# main_card_relay.net
KiCad netlist of a schematic drawn in EAGLE
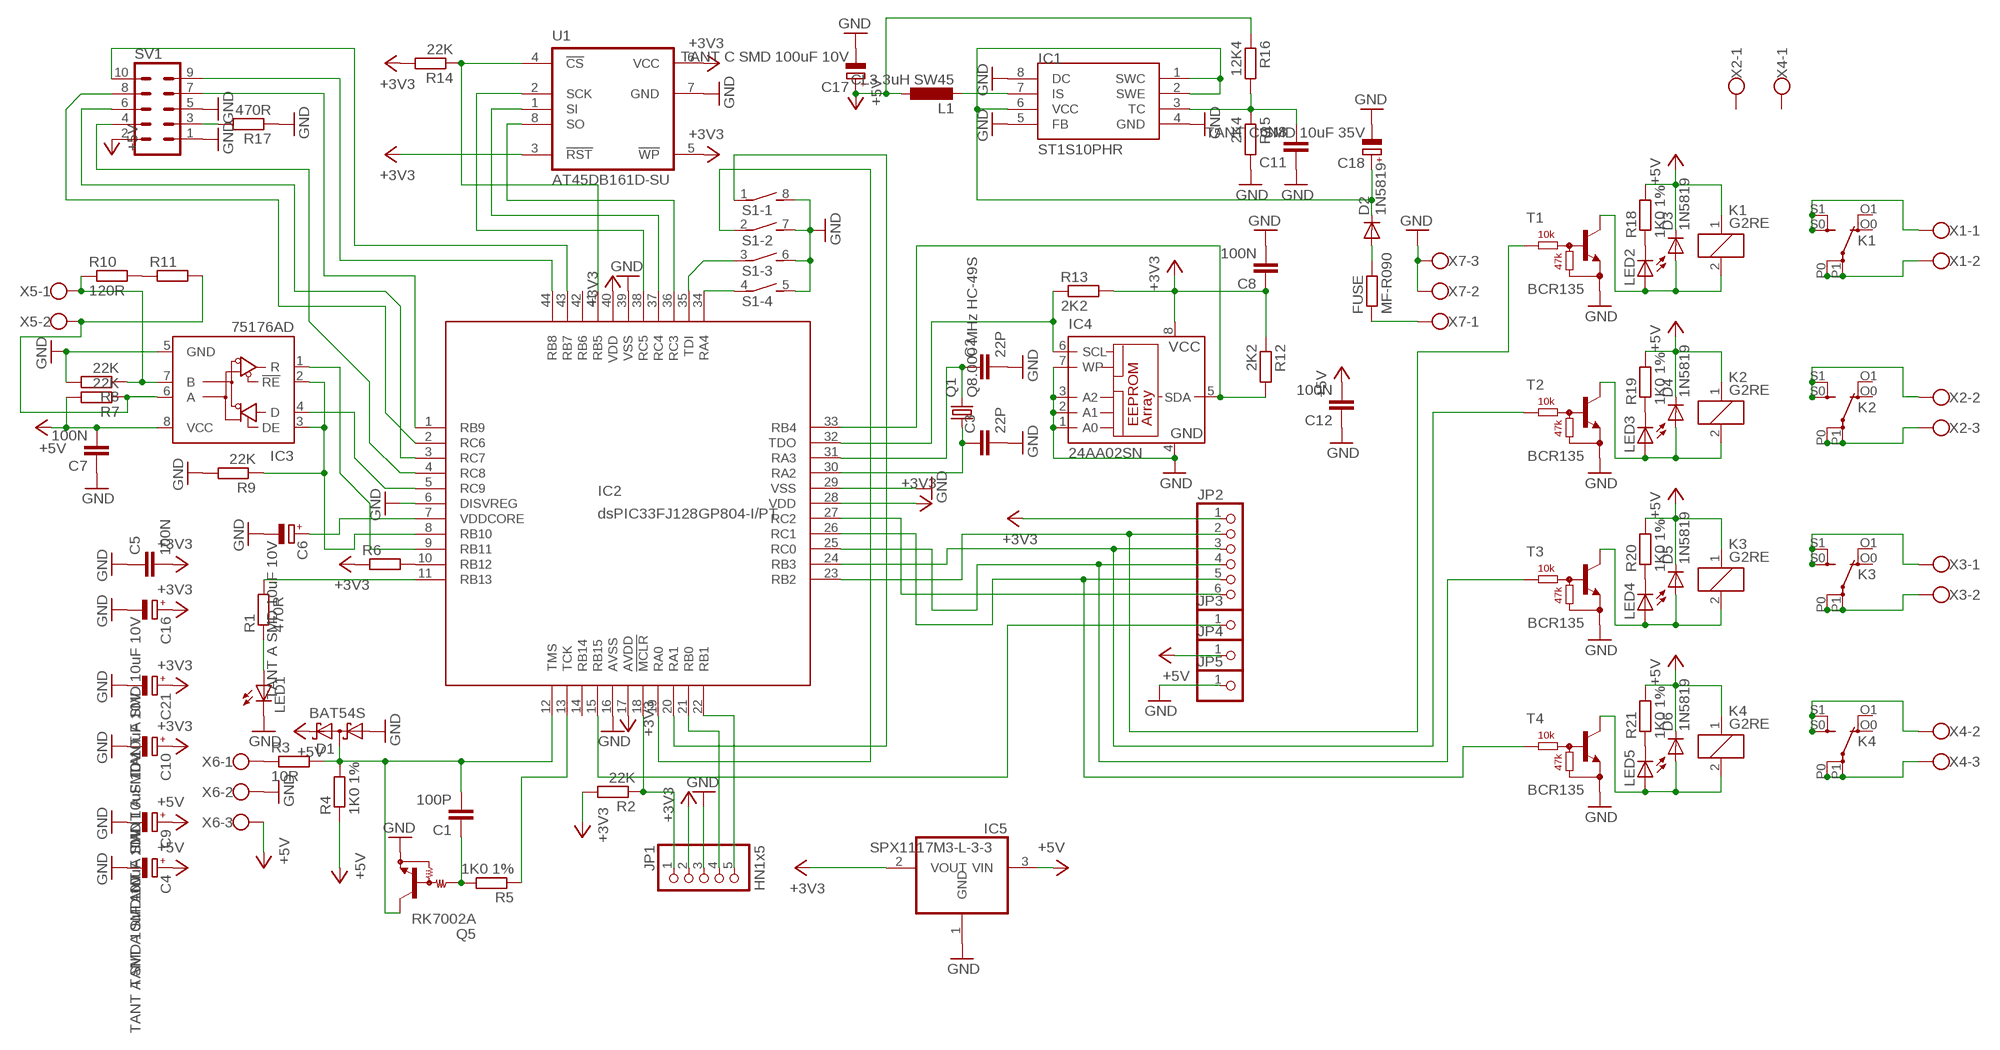
[diagram p0: schematic, sheet 1]

(export (version "E")
  (design (tool "Eeschema 10.0.6"))
  (components
    (comp (ref "C1")
      (value "100P")
      (footprint "eagle-import:C0805")
      (libsource (lib "eagle-import") (part "C-EUC0805"))
    )
    (comp (ref "C2")
      (value "22P")
      (footprint "eagle-import:C0805")
      (libsource (lib "eagle-import") (part "C-EUC0805"))
    )
    (comp (ref "C3")
      (value "22P")
      (footprint "eagle-import:C0805")
      (libsource (lib "eagle-import") (part "C-EUC0805"))
    )
    (comp (ref "C4")
      (value "TANT A SMD 10uF 10V")
      (footprint "eagle-import:SMC_A")
      (libsource (lib "eagle-import") (part "CPOL-EUSMCA"))
    )
    (comp (ref "C5")
      (value "100N")
      (footprint "eagle-import:C0805")
      (libsource (lib "eagle-import") (part "C-EUC0805"))
    )
    (comp (ref "C6")
      (value "TANT A SMD 10uF 10V")
      (footprint "eagle-import:SMC_A")
      (libsource (lib "eagle-import") (part "CPOL-EUSMCA"))
    )
    (comp (ref "C7")
      (value "100N")
      (footprint "eagle-import:C0805")
      (libsource (lib "eagle-import") (part "C-EUC0805"))
    )
    (comp (ref "C8")
      (value "100N")
      (footprint "eagle-import:C0805")
      (libsource (lib "eagle-import") (part "C-EUC0805"))
    )
    (comp (ref "C9")
      (value "TANT A SMD 10uF 10V")
      (footprint "eagle-import:SMC_A")
      (libsource (lib "eagle-import") (part "CPOL-EUSMCA"))
    )
    (comp (ref "C10")
      (value "TANT A SMD 10uF 10V")
      (footprint "eagle-import:SMC_A")
      (libsource (lib "eagle-import") (part "CPOL-EUSMCA"))
    )
    (comp (ref "C11")
      (value "6N8")
      (footprint "eagle-import:C0805")
      (libsource (lib "eagle-import") (part "C-EUC0805"))
    )
    (comp (ref "C12")
      (value "100N")
      (footprint "eagle-import:C0805")
      (libsource (lib "eagle-import") (part "C-EUC0805"))
    )
    (comp (ref "C16")
      (value "TANT A SMD 10uF 10V")
      (footprint "eagle-import:SMC_A")
      (libsource (lib "eagle-import") (part "CPOL-EUSMCA"))
    )
    (comp (ref "C17")
      (value "TANT C SMD 100uF 10V")
      (footprint "eagle-import:SMC_C")
      (libsource (lib "eagle-import") (part "CPOL-EUSMCC"))
    )
    (comp (ref "C18")
      (value "TANT C SMD 10uF 35V")
      (footprint "eagle-import:SMC_C")
      (libsource (lib "eagle-import") (part "CPOL-EUSMCC"))
    )
    (comp (ref "C21")
      (value "TANT A SMD 10uF 10V")
      (footprint "eagle-import:SMC_A")
      (libsource (lib "eagle-import") (part "CPOL-EUSMCA"))
    )
    (comp (ref "D1")
      (value "BAT54S")
      (footprint "eagle-import:SOT23")
      (libsource (lib "eagle-import") (part "BAS40-04"))
    )
    (comp (ref "D2")
      (value "1N5819")
      (footprint "eagle-import:DO214AC")
      (libsource (lib "eagle-import") (part "DIODE-DO214AC"))
    )
    (comp (ref "D3")
      (value "1N5819")
      (footprint "eagle-import:DO214AC")
      (libsource (lib "eagle-import") (part "DIODE-DO214AC"))
    )
    (comp (ref "D4")
      (value "1N5819")
      (footprint "eagle-import:DO214AC")
      (libsource (lib "eagle-import") (part "DIODE-DO214AC"))
    )
    (comp (ref "D5")
      (value "1N5819")
      (footprint "eagle-import:DO214AC")
      (libsource (lib "eagle-import") (part "DIODE-DO214AC"))
    )
    (comp (ref "D6")
      (value "1N5819")
      (footprint "eagle-import:DO214AC")
      (libsource (lib "eagle-import") (part "DIODE-DO214AC"))
    )
    (comp (ref "FUSE")
      (value "MF-R090")
      (footprint "eagle-import:0204V")
      (libsource (lib "eagle-import") (part "R-EU_0204/2V"))
    )
    (comp (ref "IC1")
      (value "ST1S10PHR")
      (footprint "eagle-import:SOIC8")
      (libsource (lib "eagle-import") (part "MC34063AD"))
    )
    (comp (ref "IC2")
      (value "dsPIC33FJ128GP804-I/PT")
      (footprint "eagle-import:TQFP44")
      (libsource (lib "eagle-import") (part "PIC24FJ64GA004"))
    )
    (comp (ref "IC3")
      (value "75176AD")
      (footprint "eagle-import:D_R-PDSO-G8")
      (libsource (lib "eagle-import") (part "75176AD"))
    )
    (comp (ref "IC4")
      (value "24AA02SN")
      (footprint "eagle-import:SO-08")
      (fields (field (name "MPN") "24AA02/SN"))
      (libsource (lib "eagle-import") (part "24SNAA02"))
    )
    (comp (ref "IC5")
      (value "SPX1117M3-L-3-3")
      (footprint "eagle-import:SOT223")
      (fields (field (name "MPN") "REG1117"))
      (libsource (lib "eagle-import") (part "REG1117"))
    )
    (comp (ref "JP1")
      (value "HN1x5")
      (footprint "eagle-import:1X05")
      (libsource (lib "eagle-import") (part "PINHD-1X5"))
    )
    (comp (ref "JP2")
      (value "PINHD-1X6")
      (footprint "eagle-import:1X06")
      (libsource (lib "eagle-import") (part "PINHD-1X6"))
    )
    (comp (ref "JP3")
      (value "PINHD-1X1")
      (footprint "eagle-import:1X01")
      (libsource (lib "eagle-import") (part "PINHD-1X1"))
    )
    (comp (ref "JP4")
      (value "PINHD-1X1")
      (footprint "eagle-import:1X01")
      (libsource (lib "eagle-import") (part "PINHD-1X1"))
    )
    (comp (ref "JP5")
      (value "PINHD-1X1")
      (footprint "eagle-import:1X01")
      (libsource (lib "eagle-import") (part "PINHD-1X1"))
    )
    (comp (ref "K1")
      (value "G2RE")
      (footprint "eagle-import:G2RE")
      (libsource (lib "eagle-import") (part "G2RE"))
    )
    (comp (ref "K2")
      (value "G2RE")
      (footprint "eagle-import:G2RE")
      (libsource (lib "eagle-import") (part "G2RE"))
    )
    (comp (ref "K3")
      (value "G2RE")
      (footprint "eagle-import:G2RE")
      (libsource (lib "eagle-import") (part "G2RE"))
    )
    (comp (ref "K4")
      (value "G2RE")
      (footprint "eagle-import:G2RE")
      (libsource (lib "eagle-import") (part "G2RE"))
    )
    (comp (ref "L1")
      (value "CL3.3uH SW45")
      (footprint "eagle-import:0207_2V")
      (libsource (lib "eagle-import") (part "L-EU0207/2V"))
    )
    (comp (ref "LED1")
      (value "LEDCHIPLED_1206")
      (footprint "eagle-import:CHIPLED_1206")
      (libsource (lib "eagle-import") (part "LEDCHIPLED_1206"))
    )
    (comp (ref "LED2")
      (value "LEDCHIPLED_1206")
      (footprint "eagle-import:CHIPLED_1206")
      (libsource (lib "eagle-import") (part "LEDCHIPLED_1206"))
    )
    (comp (ref "LED3")
      (value "LEDCHIPLED_1206")
      (footprint "eagle-import:CHIPLED_1206")
      (libsource (lib "eagle-import") (part "LEDCHIPLED_1206"))
    )
    (comp (ref "LED4")
      (value "LEDCHIPLED_1206")
      (footprint "eagle-import:CHIPLED_1206")
      (libsource (lib "eagle-import") (part "LEDCHIPLED_1206"))
    )
    (comp (ref "LED5")
      (value "LEDCHIPLED_1206")
      (footprint "eagle-import:CHIPLED_1206")
      (libsource (lib "eagle-import") (part "LEDCHIPLED_1206"))
    )
    (comp (ref "Q1")
      (value "Q8.000 MHz HC-49S")
      (footprint "eagle-import:HC49_S")
      (libsource (lib "eagle-import") (part "CRYSTALHC49S"))
    )
    (comp (ref "Q5")
      (value "RK7002A")
      (footprint "eagle-import:SC59-BEC")
      (libsource (lib "eagle-import") (part "MUN2214T1"))
    )
    (comp (ref "R1")
      (value "470R")
      (footprint "eagle-import:R0805")
      (libsource (lib "eagle-import") (part "R-EU_R0805"))
    )
    (comp (ref "R2")
      (value "22K")
      (footprint "eagle-import:R0805")
      (libsource (lib "eagle-import") (part "R-EU_R0805"))
    )
    (comp (ref "R3")
      (value "10R")
      (footprint "eagle-import:R0805")
      (libsource (lib "eagle-import") (part "R-EU_R0805"))
    )
    (comp (ref "R4")
      (value "1K0 1%")
      (footprint "eagle-import:R0805")
      (libsource (lib "eagle-import") (part "R-EU_R0805"))
    )
    (comp (ref "R5")
      (value "1K0 1%")
      (footprint "eagle-import:R0805")
      (libsource (lib "eagle-import") (part "R-EU_R0805"))
    )
    (comp (ref "R6")
      (value "R-EU_R0201")
      (footprint "eagle-import:R0201")
      (libsource (lib "eagle-import") (part "R-EU_R0201"))
    )
    (comp (ref "R7")
      (value "22K")
      (footprint "eagle-import:R0805")
      (libsource (lib "eagle-import") (part "R-EU_R0805"))
    )
    (comp (ref "R8")
      (value "22K")
      (footprint "eagle-import:R0805")
      (libsource (lib "eagle-import") (part "R-EU_R0805"))
    )
    (comp (ref "R9")
      (value "22K")
      (footprint "eagle-import:R0805")
      (libsource (lib "eagle-import") (part "R-EU_R0805"))
    )
    (comp (ref "R10")
      (value "120R")
      (footprint "eagle-import:R0805")
      (libsource (lib "eagle-import") (part "R-EU_R0805"))
    )
    (comp (ref "R11")
      (value "R-EU_R0201")
      (footprint "eagle-import:R0201")
      (libsource (lib "eagle-import") (part "R-EU_R0201"))
    )
    (comp (ref "R12")
      (value "2K2")
      (footprint "eagle-import:R0805")
      (libsource (lib "eagle-import") (part "R-EU_R0805"))
    )
    (comp (ref "R13")
      (value "2K2")
      (footprint "eagle-import:R0805")
      (libsource (lib "eagle-import") (part "R-EU_R0805"))
    )
    (comp (ref "R14")
      (value "22K")
      (footprint "eagle-import:R0805")
      (libsource (lib "eagle-import") (part "R-EU_R0805"))
    )
    (comp (ref "R15")
      (value "2K4")
      (footprint "eagle-import:R0805")
      (libsource (lib "eagle-import") (part "R-EU_R0805"))
    )
    (comp (ref "R16")
      (value "12K4")
      (footprint "eagle-import:R0805")
      (libsource (lib "eagle-import") (part "R-EU_R0805"))
    )
    (comp (ref "R17")
      (value "470R")
      (footprint "eagle-import:R0805")
      (libsource (lib "eagle-import") (part "R-EU_R0805"))
    )
    (comp (ref "R18")
      (value "1K0 1%")
      (footprint "eagle-import:R0805")
      (libsource (lib "eagle-import") (part "R-EU_R0805"))
    )
    (comp (ref "R19")
      (value "1K0 1%")
      (footprint "eagle-import:R0805")
      (libsource (lib "eagle-import") (part "R-EU_R0805"))
    )
    (comp (ref "R20")
      (value "1K0 1%")
      (footprint "eagle-import:R0805")
      (libsource (lib "eagle-import") (part "R-EU_R0805"))
    )
    (comp (ref "R21")
      (value "1K0 1%")
      (footprint "eagle-import:R0805")
      (libsource (lib "eagle-import") (part "R-EU_R0805"))
    )
    (comp (ref "S1")
      (value "DIP04S")
      (footprint "eagle-import:DIP04S")
      (libsource (lib "eagle-import") (part "DIP04S"))
    )
    (comp (ref "SV1")
      (value "ML10")
      (footprint "eagle-import:ML10")
      (libsource (lib "eagle-import") (part "ML10"))
    )
    (comp (ref "T1")
      (value "BCR135")
      (footprint "eagle-import:SOT23-R_INFINEON")
      (libsource (lib "eagle-import") (part "BCR135"))
    )
    (comp (ref "T2")
      (value "BCR135")
      (footprint "eagle-import:SOT23-R_INFINEON")
      (libsource (lib "eagle-import") (part "BCR135"))
    )
    (comp (ref "T3")
      (value "BCR135")
      (footprint "eagle-import:SOT23-R_INFINEON")
      (libsource (lib "eagle-import") (part "BCR135"))
    )
    (comp (ref "T4")
      (value "BCR135")
      (footprint "eagle-import:SOT23-R_INFINEON")
      (libsource (lib "eagle-import") (part "BCR135"))
    )
    (comp (ref "U1")
      (value "AT45DB161D-SU")
      (footprint "eagle-import:SO08-8S2")
      (libsource (lib "eagle-import") (part "AT45DB011D-S"))
    )
    (comp (ref "X1")
      (value "W237-102")
      (footprint "eagle-import:W237-102")
      (fields (field (name "MPN") "237-102"))
      (libsource (lib "eagle-import") (part "W237-102"))
    )
    (comp (ref "X2")
      (value "W237-103")
      (footprint "eagle-import:W237-103")
      (fields (field (name "MPN") "237-103"))
      (libsource (lib "eagle-import") (part "W237-103"))
    )
    (comp (ref "X3")
      (value "W237-102")
      (footprint "eagle-import:W237-102")
      (fields (field (name "MPN") "237-102"))
      (libsource (lib "eagle-import") (part "W237-102"))
    )
    (comp (ref "X4")
      (value "W237-103")
      (footprint "eagle-import:W237-103")
      (fields (field (name "MPN") "237-103"))
      (libsource (lib "eagle-import") (part "W237-103"))
    )
    (comp (ref "X5")
      (value "W237-102")
      (footprint "eagle-import:W237-102")
      (fields (field (name "MPN") "237-102"))
      (libsource (lib "eagle-import") (part "W237-102"))
    )
    (comp (ref "X6")
      (value "W237-103")
      (footprint "eagle-import:W237-103")
      (fields (field (name "MPN") "237-103"))
      (libsource (lib "eagle-import") (part "W237-103"))
    )
    (comp (ref "X7")
      (value "W237-103")
      (footprint "eagle-import:W237-103")
      (fields (field (name "MPN") "237-103"))
      (libsource (lib "eagle-import") (part "W237-103"))
    )
  )
  (nets
    (net (code "1") (name "+3V3") (class "Default")
      (node (ref "C10") (pin "+") (pinfunction "+_+") (pintype "passive"))
      (node (ref "C16") (pin "+") (pinfunction "+_+") (pintype "passive"))
      (node (ref "C21") (pin "+") (pinfunction "+_+") (pintype "passive"))
      (node (ref "C5") (pin "2") (pinfunction "2_2") (pintype "passive"))
      (node (ref "C8") (pin "1") (pinfunction "1_1") (pintype "passive"))
      (node (ref "IC2") (pin "17") (pinfunction "AVDD_17") (pintype "power_in"))
      (node (ref "IC2") (pin "28") (pinfunction "VDD_28") (pintype "power_in"))
      (node (ref "IC2") (pin "40") (pinfunction "VDD_40") (pintype "power_in"))
      (node (ref "IC4") (pin "8") (pinfunction "VCC_8") (pintype "power_in"))
      (node (ref "IC5") (pin "2") (pinfunction "VOUT_2") (pintype "output"))
      (node (ref "JP1") (pin "2") (pinfunction "2_2") (pintype "passive"))
      (node (ref "JP2") (pin "1") (pinfunction "1_1") (pintype "passive"))
      (node (ref "R12") (pin "1") (pinfunction "1_1") (pintype "passive"))
      (node (ref "R13") (pin "2") (pinfunction "2_2") (pintype "passive"))
      (node (ref "R14") (pin "2") (pinfunction "2_2") (pintype "passive"))
      (node (ref "R2") (pin "2") (pinfunction "2_2") (pintype "passive"))
      (node (ref "R6") (pin "1") (pinfunction "1_1") (pintype "passive"))
      (node (ref "U1") (pin "3") (pinfunction "~{RST}_3") (pintype "bidirectional"))
      (node (ref "U1") (pin "5") (pinfunction "~{WP}_5") (pintype "bidirectional"))
      (node (ref "U1") (pin "6") (pinfunction "VCC_6") (pintype "power_in"))
    )
    (net (code "2") (name "+5V") (class "Default")
      (node (ref "C12") (pin "2") (pinfunction "2_2") (pintype "passive"))
      (node (ref "C17") (pin "+") (pinfunction "+_+") (pintype "passive"))
      (node (ref "C4") (pin "+") (pinfunction "+_+") (pintype "passive"))
      (node (ref "C7") (pin "2") (pinfunction "2_2") (pintype "passive"))
      (node (ref "C9") (pin "+") (pinfunction "+_+") (pintype "passive"))
      (node (ref "D1") (pin "2") (pinfunction "C2_2") (pintype "passive"))
      (node (ref "D3") (pin "C") (pinfunction "C_C") (pintype "passive"))
      (node (ref "D4") (pin "C") (pinfunction "C_C") (pintype "passive"))
      (node (ref "D5") (pin "C") (pinfunction "C_C") (pintype "passive"))
      (node (ref "D6") (pin "C") (pinfunction "C_C") (pintype "passive"))
      (node (ref "IC3") (pin "8") (pinfunction "VCC_8") (pintype "power_in"))
      (node (ref "IC5") (pin "3") (pinfunction "VIN_3") (pintype "input"))
      (node (ref "JP4") (pin "1") (pinfunction "1_1") (pintype "passive"))
      (node (ref "K1") (pin "1") (pinfunction "1_1") (pintype "passive"))
      (node (ref "K2") (pin "1") (pinfunction "1_1") (pintype "passive"))
      (node (ref "K3") (pin "1") (pinfunction "1_1") (pintype "passive"))
      (node (ref "K4") (pin "1") (pinfunction "1_1") (pintype "passive"))
      (node (ref "L1") (pin "1") (pinfunction "1_1") (pintype "passive"))
      (node (ref "R16") (pin "1") (pinfunction "1_1") (pintype "passive"))
      (node (ref "R18") (pin "2") (pinfunction "2_2") (pintype "passive"))
      (node (ref "R19") (pin "2") (pinfunction "2_2") (pintype "passive"))
      (node (ref "R20") (pin "2") (pinfunction "2_2") (pintype "passive"))
      (node (ref "R21") (pin "2") (pinfunction "2_2") (pintype "passive"))
      (node (ref "R4") (pin "1") (pinfunction "1_1") (pintype "passive"))
      (node (ref "R7") (pin "2") (pinfunction "2_2") (pintype "passive"))
      (node (ref "SV1") (pin "2") (pinfunction "2_2") (pintype "passive"))
      (node (ref "X6") (pin "3") (pinfunction "KL_3") (pintype "passive"))
    )
    (net (code "3") (name "GND") (class "Default")
      (node (ref "C10") (pin "-") (pinfunction "-_-") (pintype "passive"))
      (node (ref "C11") (pin "1") (pinfunction "1_1") (pintype "passive"))
      (node (ref "C12") (pin "1") (pinfunction "1_1") (pintype "passive"))
      (node (ref "C16") (pin "-") (pinfunction "-_-") (pintype "passive"))
      (node (ref "C17") (pin "-") (pinfunction "-_-") (pintype "passive"))
      (node (ref "C18") (pin "-") (pinfunction "-_-") (pintype "passive"))
      (node (ref "C2") (pin "2") (pinfunction "2_2") (pintype "passive"))
      (node (ref "C21") (pin "-") (pinfunction "-_-") (pintype "passive"))
      (node (ref "C3") (pin "2") (pinfunction "2_2") (pintype "passive"))
      (node (ref "C4") (pin "-") (pinfunction "-_-") (pintype "passive"))
      (node (ref "C5") (pin "1") (pinfunction "1_1") (pintype "passive"))
      (node (ref "C6") (pin "-") (pinfunction "-_-") (pintype "passive"))
      (node (ref "C7") (pin "1") (pinfunction "1_1") (pintype "passive"))
      (node (ref "C8") (pin "2") (pinfunction "2_2") (pintype "passive"))
      (node (ref "C9") (pin "-") (pinfunction "-_-") (pintype "passive"))
      (node (ref "D1") (pin "1") (pinfunction "A1_1") (pintype "passive"))
      (node (ref "IC1") (pin "4") (pinfunction "GND_4") (pintype "passive"))
      (node (ref "IC1") (pin "5") (pinfunction "FB_5") (pintype "passive"))
      (node (ref "IC1") (pin "8") (pinfunction "DC_8") (pintype "passive"))
      (node (ref "IC2") (pin "16") (pinfunction "AVSS_16") (pintype "power_in"))
      (node (ref "IC2") (pin "29") (pinfunction "VSS_29") (pintype "power_in"))
      (node (ref "IC2") (pin "39") (pinfunction "VSS_39") (pintype "power_in"))
      (node (ref "IC2") (pin "6") (pinfunction "DISVREG_6") (pintype "passive"))
      (node (ref "IC3") (pin "5") (pinfunction "GND_5") (pintype "power_in"))
      (node (ref "IC4") (pin "1") (pinfunction "A0_1") (pintype "input"))
      (node (ref "IC4") (pin "2") (pinfunction "A1_2") (pintype "input"))
      (node (ref "IC4") (pin "3") (pinfunction "A2_3") (pintype "input"))
      (node (ref "IC4") (pin "4") (pinfunction "GND_4") (pintype "power_in"))
      (node (ref "IC4") (pin "7") (pinfunction "WP_7") (pintype "input"))
      (node (ref "IC5") (pin "1") (pinfunction "GND_1") (pintype "power_in"))
      (node (ref "JP1") (pin "3") (pinfunction "3_3") (pintype "passive"))
      (node (ref "JP5") (pin "1") (pinfunction "1_1") (pintype "passive"))
      (node (ref "LED1") (pin "C") (pinfunction "C_C") (pintype "passive"))
      (node (ref "Q5") (pin "E") (pinfunction "E_E") (pintype "passive"))
      (node (ref "R15") (pin "2") (pinfunction "2_2") (pintype "passive"))
      (node (ref "R17") (pin "1") (pinfunction "1_1") (pintype "passive"))
      (node (ref "R8") (pin "2") (pinfunction "2_2") (pintype "passive"))
      (node (ref "R9") (pin "2") (pinfunction "2_2") (pintype "passive"))
      (node (ref "S1") (pin "5") (pinfunction "2_5") (pintype "passive"))
      (node (ref "S1") (pin "6") (pinfunction "2_6") (pintype "passive"))
      (node (ref "S1") (pin "7") (pinfunction "2_7") (pintype "passive"))
      (node (ref "S1") (pin "8") (pinfunction "2_8") (pintype "passive"))
      (node (ref "SV1") (pin "1") (pinfunction "1_1") (pintype "passive"))
      (node (ref "SV1") (pin "5") (pinfunction "5_5") (pintype "passive"))
      (node (ref "T1") (pin "2") (pinfunction "E_2") (pintype "passive"))
      (node (ref "T2") (pin "2") (pinfunction "E_2") (pintype "passive"))
      (node (ref "T3") (pin "2") (pinfunction "E_2") (pintype "passive"))
      (node (ref "T4") (pin "2") (pinfunction "E_2") (pintype "passive"))
      (node (ref "U1") (pin "7") (pinfunction "GND_7") (pintype "power_in"))
      (node (ref "X6") (pin "2") (pinfunction "KL_2") (pintype "passive"))
      (node (ref "X7") (pin "2") (pinfunction "KL_2") (pintype "passive"))
      (node (ref "X7") (pin "3") (pinfunction "KL_3") (pintype "passive"))
    )
    (net (code "4") (name "Net-(C1-Pad1)") (class "Default")
      (node (ref "C1") (pin "1") (pinfunction "1_1") (pintype "passive"))
      (node (ref "Q5") (pin "B") (pinfunction "B_B") (pintype "passive"))
      (node (ref "R5") (pin "2") (pinfunction "2_2") (pintype "passive"))
    )
    (net (code "5") (name "Net-(D1-C1A2)") (class "Default")
      (node (ref "C1") (pin "2") (pinfunction "2_2") (pintype "passive"))
      (node (ref "D1") (pin "3") (pinfunction "C1A2_3") (pintype "passive"))
      (node (ref "IC2") (pin "12") (pinfunction "TMS_12") (pintype "input"))
      (node (ref "Q5") (pin "C") (pinfunction "C_C") (pintype "passive"))
      (node (ref "R3") (pin "2") (pinfunction "2_2") (pintype "passive"))
      (node (ref "R4") (pin "2") (pinfunction "2_2") (pintype "passive"))
    )
    (net (code "6") (name "Net-(D2-PadA)") (class "Default")
      (node (ref "D2") (pin "A") (pinfunction "A_A") (pintype "passive"))
      (node (ref "FUSE") (pin "2") (pinfunction "2_2") (pintype "passive"))
    )
    (net (code "7") (name "Net-(IC1-IS)") (class "Default")
      (node (ref "IC1") (pin "7") (pinfunction "IS_7") (pintype "passive"))
      (node (ref "L1") (pin "2") (pinfunction "2_2") (pintype "passive"))
    )
    (net (code "8") (name "Net-(IC1-SWC)") (class "Default")
      (node (ref "C18") (pin "+") (pinfunction "+_+") (pintype "passive"))
      (node (ref "D2") (pin "C") (pinfunction "C_C") (pintype "passive"))
      (node (ref "IC1") (pin "1") (pinfunction "SWC_1") (pintype "passive"))
      (node (ref "IC1") (pin "2") (pinfunction "SWE_2") (pintype "passive"))
      (node (ref "IC1") (pin "6") (pinfunction "VCC_6") (pintype "passive"))
    )
    (net (code "9") (name "Net-(IC1-TC)") (class "Default")
      (node (ref "C11") (pin "2") (pinfunction "2_2") (pintype "passive"))
      (node (ref "IC1") (pin "3") (pinfunction "TC_3") (pintype "passive"))
      (node (ref "R15") (pin "1") (pinfunction "1_1") (pintype "passive"))
      (node (ref "R16") (pin "2") (pinfunction "2_2") (pintype "passive"))
    )
    (net (code "10") (name "Net-(IC2-RA0)") (class "Default")
      (node (ref "IC2") (pin "19") (pinfunction "RA0_19") (pintype "bidirectional"))
      (node (ref "S1") (pin "2") (pinfunction "1_2") (pintype "passive"))
    )
    (net (code "11") (name "Net-(IC2-RA1)") (class "Default")
      (node (ref "IC2") (pin "20") (pinfunction "RA1_20") (pintype "bidirectional"))
      (node (ref "S1") (pin "1") (pinfunction "1_1") (pintype "passive"))
    )
    (net (code "12") (name "Net-(IC2-RA2)") (class "Default")
      (node (ref "C3") (pin "1") (pinfunction "1_1") (pintype "passive"))
      (node (ref "IC2") (pin "30") (pinfunction "RA2_30") (pintype "bidirectional"))
      (node (ref "Q1") (pin "1") (pinfunction "1_1") (pintype "passive"))
    )
    (net (code "13") (name "Net-(IC2-RA3)") (class "Default")
      (node (ref "C2") (pin "1") (pinfunction "1_1") (pintype "passive"))
      (node (ref "IC2") (pin "31") (pinfunction "RA3_31") (pintype "bidirectional"))
      (node (ref "Q1") (pin "2") (pinfunction "2_2") (pintype "passive"))
    )
    (net (code "14") (name "Net-(IC2-RA4)") (class "Default")
      (node (ref "IC2") (pin "34") (pinfunction "RA4_34") (pintype "bidirectional"))
      (node (ref "S1") (pin "4") (pinfunction "1_4") (pintype "passive"))
    )
    (net (code "15") (name "Net-(IC2-RB0)") (class "Default")
      (node (ref "IC2") (pin "21") (pinfunction "RB0_21") (pintype "bidirectional"))
      (node (ref "JP1") (pin "4") (pinfunction "4_4") (pintype "passive"))
    )
    (net (code "16") (name "Net-(IC2-RB1)") (class "Default")
      (node (ref "IC2") (pin "22") (pinfunction "RB1_22") (pintype "bidirectional"))
      (node (ref "JP1") (pin "5") (pinfunction "5_5") (pintype "passive"))
    )
    (net (code "17") (name "Net-(IC2-RB2)") (class "Default")
      (node (ref "IC2") (pin "23") (pinfunction "RB2_23") (pintype "bidirectional"))
      (node (ref "JP2") (pin "2") (pinfunction "2_2") (pintype "passive"))
      (node (ref "T1") (pin "1") (pinfunction "B_1") (pintype "passive"))
    )
    (net (code "18") (name "Net-(IC2-RB3)") (class "Default")
      (node (ref "IC2") (pin "24") (pinfunction "RB3_24") (pintype "bidirectional"))
      (node (ref "JP2") (pin "3") (pinfunction "3_3") (pintype "passive"))
      (node (ref "T2") (pin "1") (pinfunction "B_1") (pintype "passive"))
    )
    (net (code "19") (name "Net-(IC2-RB4)") (class "Default")
      (node (ref "IC2") (pin "33") (pinfunction "RB4_33") (pintype "bidirectional"))
      (node (ref "IC4") (pin "5") (pinfunction "SDA_5") (pintype "bidirectional"))
      (node (ref "R12") (pin "2") (pinfunction "2_2") (pintype "passive"))
    )
    (net (code "20") (name "Net-(IC2-RB5)") (class "Default")
      (node (ref "IC2") (pin "41") (pinfunction "RB5_41") (pintype "bidirectional"))
      (node (ref "R14") (pin "1") (pinfunction "1_1") (pintype "passive"))
      (node (ref "U1") (pin "4") (pinfunction "~{CS}_4") (pintype "bidirectional"))
    )
    (net (code "21") (name "Net-(IC2-RB7)") (class "Default")
      (node (ref "IC2") (pin "43") (pinfunction "RB7_43") (pintype "bidirectional"))
      (node (ref "SV1") (pin "10") (pinfunction "10_10") (pintype "passive"))
    )
    (net (code "22") (name "Net-(IC2-RB8)") (class "Default")
      (node (ref "IC2") (pin "44") (pinfunction "RB8_44") (pintype "bidirectional"))
      (node (ref "SV1") (pin "9") (pinfunction "9_9") (pintype "passive"))
    )
    (net (code "23") (name "Net-(IC2-RB9)") (class "Default")
      (node (ref "IC2") (pin "1") (pinfunction "RB9_1") (pintype "bidirectional"))
      (node (ref "SV1") (pin "7") (pinfunction "7_7") (pintype "passive"))
    )
    (net (code "24") (name "Net-(IC2-RB10)") (class "Default")
      (node (ref "IC2") (pin "8") (pinfunction "RB10_8") (pintype "bidirectional"))
      (node (ref "IC3") (pin "2") (pinfunction "~{RE}_2") (pintype "input"))
      (node (ref "IC3") (pin "3") (pinfunction "DE_3") (pintype "input"))
      (node (ref "R9") (pin "1") (pinfunction "1_1") (pintype "passive"))
    )
    (net (code "25") (name "Net-(IC2-RB11)") (class "Default")
      (node (ref "IC2") (pin "9") (pinfunction "RB11_9") (pintype "bidirectional"))
      (node (ref "IC3") (pin "1") (pinfunction "R_1") (pintype "input"))
    )
    (net (code "26") (name "Net-(IC2-RB12)") (class "Default")
      (node (ref "IC2") (pin "10") (pinfunction "RB12_10") (pintype "bidirectional"))
      (node (ref "R6") (pin "2") (pinfunction "2_2") (pintype "passive"))
    )
    (net (code "27") (name "Net-(IC2-RB13)") (class "Default")
      (node (ref "IC2") (pin "11") (pinfunction "RB13_11") (pintype "bidirectional"))
      (node (ref "R1") (pin "2") (pinfunction "2_2") (pintype "passive"))
    )
    (net (code "28") (name "Net-(IC2-RB15)") (class "Default")
      (node (ref "IC2") (pin "15") (pinfunction "RB15_15") (pintype "bidirectional"))
      (node (ref "JP3") (pin "1") (pinfunction "1_1") (pintype "passive"))
    )
    (net (code "29") (name "Net-(IC2-RC0)") (class "Default")
      (node (ref "IC2") (pin "25") (pinfunction "RC0_25") (pintype "bidirectional"))
      (node (ref "JP2") (pin "4") (pinfunction "4_4") (pintype "passive"))
      (node (ref "T3") (pin "1") (pinfunction "B_1") (pintype "passive"))
    )
    (net (code "30") (name "Net-(IC2-RC1)") (class "Default")
      (node (ref "IC2") (pin "26") (pinfunction "RC1_26") (pintype "bidirectional"))
      (node (ref "JP2") (pin "5") (pinfunction "5_5") (pintype "passive"))
      (node (ref "T4") (pin "1") (pinfunction "B_1") (pintype "passive"))
    )
    (net (code "31") (name "Net-(IC2-RC2)") (class "Default")
      (node (ref "IC2") (pin "27") (pinfunction "RC2_27") (pintype "bidirectional"))
      (node (ref "JP2") (pin "6") (pinfunction "6_6") (pintype "passive"))
    )
    (net (code "32") (name "Net-(IC2-RC3)") (class "Default")
      (node (ref "IC2") (pin "36") (pinfunction "RC3_36") (pintype "bidirectional"))
      (node (ref "U1") (pin "8") (pinfunction "SO_8") (pintype "bidirectional"))
    )
    (net (code "33") (name "Net-(IC2-RC4)") (class "Default")
      (node (ref "IC2") (pin "37") (pinfunction "RC4_37") (pintype "bidirectional"))
      (node (ref "U1") (pin "1") (pinfunction "SI_1") (pintype "bidirectional"))
    )
    (net (code "34") (name "Net-(IC2-RC5)") (class "Default")
      (node (ref "IC2") (pin "38") (pinfunction "RC5_38") (pintype "bidirectional"))
      (node (ref "U1") (pin "2") (pinfunction "SCK_2") (pintype "bidirectional"))
    )
    (net (code "35") (name "Net-(IC2-RC6)") (class "Default")
      (node (ref "IC2") (pin "2") (pinfunction "RC6_2") (pintype "bidirectional"))
      (node (ref "SV1") (pin "8") (pinfunction "8_8") (pintype "passive"))
    )
    (net (code "36") (name "Net-(IC2-RC7)") (class "Default")
      (node (ref "IC2") (pin "3") (pinfunction "RC7_3") (pintype "bidirectional"))
      (node (ref "SV1") (pin "6") (pinfunction "6_6") (pintype "passive"))
    )
    (net (code "37") (name "Net-(IC2-RC8)") (class "Default")
      (node (ref "IC2") (pin "4") (pinfunction "RC8_4") (pintype "bidirectional"))
      (node (ref "SV1") (pin "4") (pinfunction "4_4") (pintype "passive"))
    )
    (net (code "38") (name "Net-(IC2-RC9)") (class "Default")
      (node (ref "IC2") (pin "5") (pinfunction "RC9_5") (pintype "bidirectional"))
      (node (ref "IC3") (pin "4") (pinfunction "D_4") (pintype "input"))
    )
    (net (code "39") (name "Net-(IC2-TCK)") (class "Default")
      (node (ref "IC2") (pin "13") (pinfunction "TCK_13") (pintype "input"))
      (node (ref "R5") (pin "1") (pinfunction "1_1") (pintype "passive"))
    )
    (net (code "40") (name "Net-(IC2-TDI)") (class "Default")
      (node (ref "IC2") (pin "35") (pinfunction "TDI_35") (pintype "input"))
      (node (ref "S1") (pin "3") (pinfunction "1_3") (pintype "passive"))
    )
    (net (code "41") (name "Net-(IC2-TDO)") (class "Default")
      (node (ref "IC2") (pin "32") (pinfunction "TDO_32") (pintype "output"))
      (node (ref "IC4") (pin "6") (pinfunction "SCL_6") (pintype "input"))
      (node (ref "R13") (pin "1") (pinfunction "1_1") (pintype "passive"))
    )
    (net (code "42") (name "Net-(IC2-VDDCORE)") (class "Default")
      (node (ref "C6") (pin "+") (pinfunction "+_+") (pintype "passive"))
      (node (ref "IC2") (pin "7") (pinfunction "VDDCORE_7") (pintype "power_in"))
    )
    (net (code "43") (name "Net-(IC2-~{MCLR})") (class "Default")
      (node (ref "IC2") (pin "18") (pinfunction "~{MCLR}_18") (pintype "bidirectional"))
      (node (ref "JP1") (pin "1") (pinfunction "1_1") (pintype "passive"))
      (node (ref "R2") (pin "1") (pinfunction "1_1") (pintype "passive"))
    )
    (net (code "44") (name "Net-(IC3-A)") (class "Default")
      (node (ref "IC3") (pin "6") (pinfunction "A_6") (pintype "output"))
      (node (ref "R11") (pin "2") (pinfunction "2_2") (pintype "passive"))
      (node (ref "R7") (pin "1") (pinfunction "1_1") (pintype "passive"))
      (node (ref "X5") (pin "2") (pinfunction "KL_2") (pintype "passive"))
    )
    (net (code "45") (name "Net-(IC3-B)") (class "Default")
      (node (ref "IC3") (pin "7") (pinfunction "B_7") (pintype "output"))
      (node (ref "R10") (pin "1") (pinfunction "1_1") (pintype "passive"))
      (node (ref "R8") (pin "1") (pinfunction "1_1") (pintype "passive"))
      (node (ref "X5") (pin "1") (pinfunction "KL_1") (pintype "passive"))
    )
    (net (code "46") (name "Net-(LED1-PadA)") (class "Default")
      (node (ref "LED1") (pin "A") (pinfunction "A_A") (pintype "passive"))
      (node (ref "R1") (pin "1") (pinfunction "1_1") (pintype "passive"))
    )
    (net (code "47") (name "Net-(LED2-PadC)") (class "Default")
      (node (ref "LED2") (pin "C") (pinfunction "C_C") (pintype "passive"))
      (node (ref "R18") (pin "1") (pinfunction "1_1") (pintype "passive"))
    )
    (net (code "48") (name "Net-(LED3-PadC)") (class "Default")
      (node (ref "LED3") (pin "C") (pinfunction "C_C") (pintype "passive"))
      (node (ref "R19") (pin "1") (pinfunction "1_1") (pintype "passive"))
    )
    (net (code "49") (name "Net-(LED4-PadC)") (class "Default")
      (node (ref "LED4") (pin "C") (pinfunction "C_C") (pintype "passive"))
      (node (ref "R20") (pin "1") (pinfunction "1_1") (pintype "passive"))
    )
    (net (code "50") (name "Net-(LED5-PadC)") (class "Default")
      (node (ref "LED5") (pin "C") (pinfunction "C_C") (pintype "passive"))
      (node (ref "R21") (pin "1") (pinfunction "1_1") (pintype "passive"))
    )
    (net (code "51") (name "Net-(R10-Pad2)") (class "Default")
      (node (ref "R10") (pin "2") (pinfunction "2_2") (pintype "passive"))
      (node (ref "R11") (pin "1") (pinfunction "1_1") (pintype "passive"))
    )
    (net (code "52") (name "Net-(R17-Pad2)") (class "Default")
      (node (ref "R17") (pin "2") (pinfunction "2_2") (pintype "passive"))
      (node (ref "SV1") (pin "3") (pinfunction "3_3") (pintype "passive"))
    )
    (net (code "53") (name "Net-(T1-C)") (class "Default")
      (node (ref "D3") (pin "A") (pinfunction "A_A") (pintype "passive"))
      (node (ref "K1") (pin "2") (pinfunction "2_2") (pintype "passive"))
      (node (ref "LED2") (pin "A") (pinfunction "A_A") (pintype "passive"))
      (node (ref "T1") (pin "3") (pinfunction "C_3") (pintype "passive"))
    )
    (net (code "54") (name "Net-(T2-C)") (class "Default")
      (node (ref "D4") (pin "A") (pinfunction "A_A") (pintype "passive"))
      (node (ref "K2") (pin "2") (pinfunction "2_2") (pintype "passive"))
      (node (ref "LED3") (pin "A") (pinfunction "A_A") (pintype "passive"))
      (node (ref "T2") (pin "3") (pinfunction "C_3") (pintype "passive"))
    )
    (net (code "55") (name "Net-(T3-C)") (class "Default")
      (node (ref "D5") (pin "A") (pinfunction "A_A") (pintype "passive"))
      (node (ref "K3") (pin "2") (pinfunction "2_2") (pintype "passive"))
      (node (ref "LED4") (pin "A") (pinfunction "A_A") (pintype "passive"))
      (node (ref "T3") (pin "3") (pinfunction "C_3") (pintype "passive"))
    )
    (net (code "56") (name "Net-(T4-C)") (class "Default")
      (node (ref "D6") (pin "A") (pinfunction "A_A") (pintype "passive"))
      (node (ref "K4") (pin "2") (pinfunction "2_2") (pintype "passive"))
      (node (ref "LED5") (pin "A") (pinfunction "A_A") (pintype "passive"))
      (node (ref "T4") (pin "3") (pinfunction "C_3") (pintype "passive"))
    )
    (net (code "57") (name "Net-(X1A-KL)") (class "Default")
      (node (ref "K1") (pin "S0") (pinfunction "S_S0") (pintype "passive"))
      (node (ref "K1") (pin "S1") (pinfunction "S_S1") (pintype "passive"))
      (node (ref "X1") (pin "1") (pinfunction "KL_1") (pintype "passive"))
    )
    (net (code "58") (name "Net-(X1B-KL)") (class "Default")
      (node (ref "K1") (pin "P0") (pinfunction "P_P0") (pintype "passive"))
      (node (ref "K1") (pin "P1") (pinfunction "P_P1") (pintype "passive"))
      (node (ref "X1") (pin "2") (pinfunction "KL_2") (pintype "passive"))
    )
    (net (code "59") (name "Net-(X2B-KL)") (class "Default")
      (node (ref "K2") (pin "S0") (pinfunction "S_S0") (pintype "passive"))
      (node (ref "K2") (pin "S1") (pinfunction "S_S1") (pintype "passive"))
      (node (ref "X2") (pin "2") (pinfunction "KL_2") (pintype "passive"))
    )
    (net (code "60") (name "Net-(X2C-KL)") (class "Default")
      (node (ref "K2") (pin "P0") (pinfunction "P_P0") (pintype "passive"))
      (node (ref "K2") (pin "P1") (pinfunction "P_P1") (pintype "passive"))
      (node (ref "X2") (pin "3") (pinfunction "KL_3") (pintype "passive"))
    )
    (net (code "61") (name "Net-(X3A-KL)") (class "Default")
      (node (ref "K3") (pin "S0") (pinfunction "S_S0") (pintype "passive"))
      (node (ref "K3") (pin "S1") (pinfunction "S_S1") (pintype "passive"))
      (node (ref "X3") (pin "1") (pinfunction "KL_1") (pintype "passive"))
    )
    (net (code "62") (name "Net-(X3B-KL)") (class "Default")
      (node (ref "K3") (pin "P0") (pinfunction "P_P0") (pintype "passive"))
      (node (ref "K3") (pin "P1") (pinfunction "P_P1") (pintype "passive"))
      (node (ref "X3") (pin "2") (pinfunction "KL_2") (pintype "passive"))
    )
    (net (code "63") (name "Net-(X4B-KL)") (class "Default")
      (node (ref "K4") (pin "S0") (pinfunction "S_S0") (pintype "passive"))
      (node (ref "K4") (pin "S1") (pinfunction "S_S1") (pintype "passive"))
      (node (ref "X4") (pin "2") (pinfunction "KL_2") (pintype "passive"))
    )
    (net (code "64") (name "Net-(X4C-KL)") (class "Default")
      (node (ref "K4") (pin "P0") (pinfunction "P_P0") (pintype "passive"))
      (node (ref "K4") (pin "P1") (pinfunction "P_P1") (pintype "passive"))
      (node (ref "X4") (pin "3") (pinfunction "KL_3") (pintype "passive"))
    )
    (net (code "65") (name "Net-(X6A-KL)") (class "Default")
      (node (ref "R3") (pin "1") (pinfunction "1_1") (pintype "passive"))
      (node (ref "X6") (pin "1") (pinfunction "KL_1") (pintype "passive"))
    )
    (net (code "66") (name "Net-(X7A-KL)") (class "Default")
      (node (ref "FUSE") (pin "1") (pinfunction "1_1") (pintype "passive"))
      (node (ref "X7") (pin "1") (pinfunction "KL_1") (pintype "passive"))
    )
    (net (code "67") (name "unconnected-(IC2-RB6-Pad42)") (class "Default")
      (node (ref "IC2") (pin "42") (pinfunction "RB6_42") (pintype "bidirectional"))
    )
    (net (code "68") (name "unconnected-(IC2-RB14-Pad14)") (class "Default")
      (node (ref "IC2") (pin "14") (pinfunction "RB14_14") (pintype "bidirectional"))
    )
    (net (code "69") (name "unconnected-(K1B-O-PadO0)") (class "Default")
      (node (ref "K1") (pin "O0") (pinfunction "O_O0") (pintype "passive"))
    )
    (net (code "70") (name "unconnected-(K1B-O-PadO1)") (class "Default")
      (node (ref "K1") (pin "O1") (pinfunction "O_O1") (pintype "passive"))
    )
    (net (code "71") (name "unconnected-(K2B-O-PadO0)") (class "Default")
      (node (ref "K2") (pin "O0") (pinfunction "O_O0") (pintype "passive"))
    )
    (net (code "72") (name "unconnected-(K2B-O-PadO1)") (class "Default")
      (node (ref "K2") (pin "O1") (pinfunction "O_O1") (pintype "passive"))
    )
    (net (code "73") (name "unconnected-(K3B-O-PadO0)") (class "Default")
      (node (ref "K3") (pin "O0") (pinfunction "O_O0") (pintype "passive"))
    )
    (net (code "74") (name "unconnected-(K3B-O-PadO1)") (class "Default")
      (node (ref "K3") (pin "O1") (pinfunction "O_O1") (pintype "passive"))
    )
    (net (code "75") (name "unconnected-(K4B-O-PadO0)") (class "Default")
      (node (ref "K4") (pin "O0") (pinfunction "O_O0") (pintype "passive"))
    )
    (net (code "76") (name "unconnected-(K4B-O-PadO1)") (class "Default")
      (node (ref "K4") (pin "O1") (pinfunction "O_O1") (pintype "passive"))
    )
    (net (code "77") (name "unconnected-(X2A-KL-Pad1)") (class "Default")
      (node (ref "X2") (pin "1") (pinfunction "KL_1") (pintype "passive"))
    )
    (net (code "78") (name "unconnected-(X4A-KL-Pad1)") (class "Default")
      (node (ref "X4") (pin "1") (pinfunction "KL_1") (pintype "passive"))
    )
  )
)
